# ws2812_Triangle.net
KiCad netlist of a schematic drawn in EAGLE
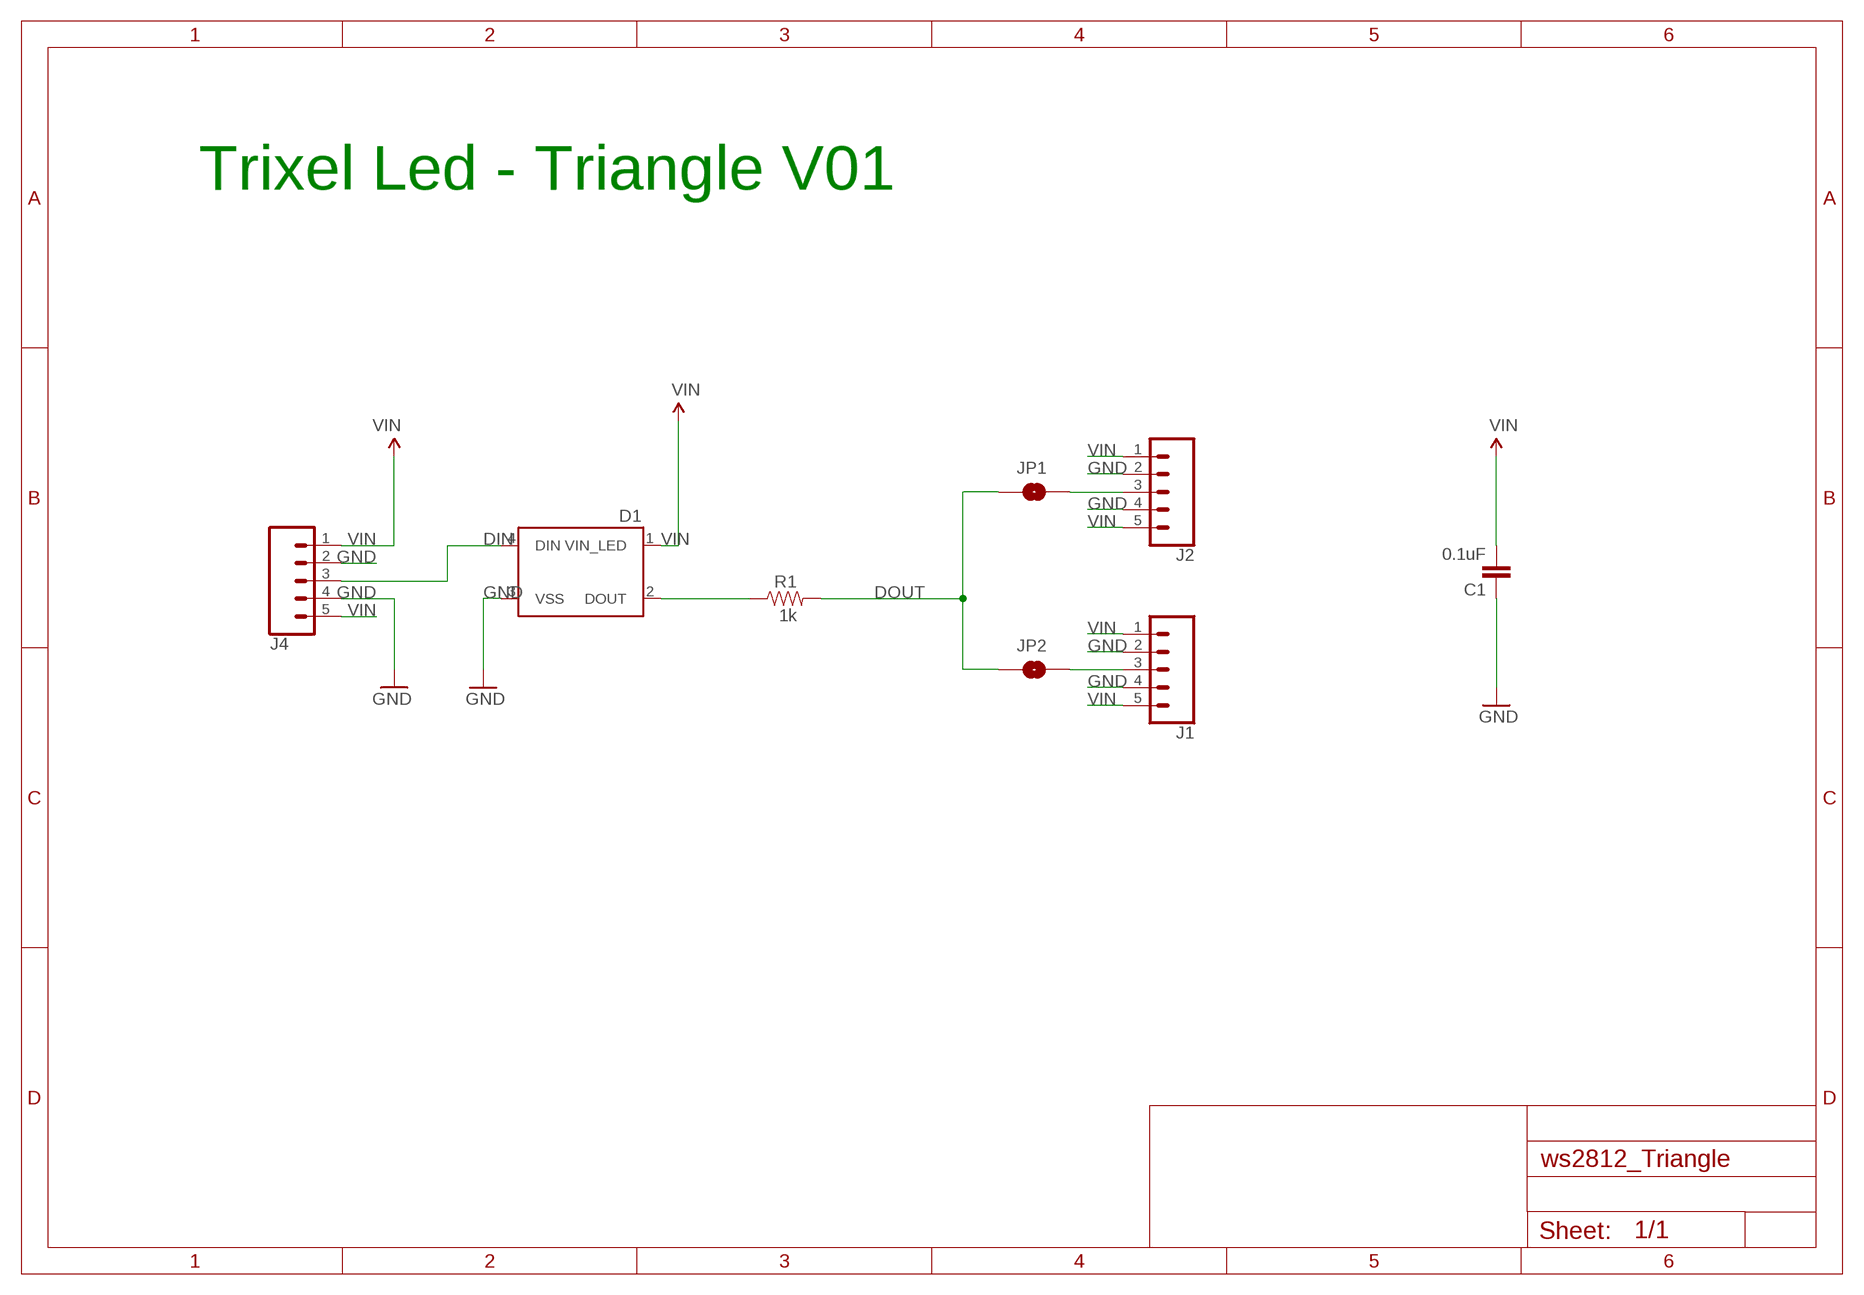
[diagram p0: schematic, sheet 1]

(export (version "E")
  (design (tool "Eeschema 10.0.6"))
  (components
    (comp (ref "C1")
      (value "0.1uF")
      (footprint "eagle-import:0805")
      (libsource (lib "eagle-import") (part "CAP0805"))
    )
    (comp (ref "D1")
      (value "WS2812B")
      (footprint "eagle-import:WS2812B")
      (libsource (lib "eagle-import") (part "WS2812B"))
    )
    (comp (ref "J1")
      (value "CONN_05PTH_LONGPADS")
      (footprint "eagle-import:1X05_LONGPADS")
      (libsource (lib "eagle-import") (part "CONN_05PTH_LONGPADS"))
    )
    (comp (ref "J2")
      (value "CONN_05PTH_LONGPADS")
      (footprint "eagle-import:1X05_LONGPADS")
      (libsource (lib "eagle-import") (part "CONN_05PTH_LONGPADS"))
    )
    (comp (ref "J4")
      (value "CONN_05PTH_LONGPADS")
      (footprint "eagle-import:1X05_LONGPADS")
      (libsource (lib "eagle-import") (part "CONN_05PTH_LONGPADS"))
    )
    (comp (ref "JP1")
      (value "JUMPER-PAD-2-NOYES_SILK")
      (footprint "eagle-import:PAD-JUMPER-2-NO_YES_SILK")
      (libsource (lib "eagle-import") (part "JUMPER-PAD-2-NOYES_SILK"))
    )
    (comp (ref "JP2")
      (value "JUMPER-PAD-2-NOYES_SILK")
      (footprint "eagle-import:PAD-JUMPER-2-NO_YES_SILK")
      (libsource (lib "eagle-import") (part "JUMPER-PAD-2-NOYES_SILK"))
    )
    (comp (ref "R1")
      (value "1k")
      (footprint "eagle-import:0805")
      (libsource (lib "eagle-import") (part "RESISTOR0805"))
    )
  )
  (nets
    (net (code "1") (name "/DIN") (class "Default")
      (node (ref "D1") (pin "4") (pinfunction "DIN_4") (pintype "input"))
      (node (ref "J4") (pin "3") (pinfunction "3_3") (pintype "passive"))
    )
    (net (code "2") (name "/DOUT") (class "Default")
      (node (ref "JP1") (pin "1") (pinfunction "1_1") (pintype "passive"))
      (node (ref "JP2") (pin "1") (pinfunction "1_1") (pintype "passive"))
      (node (ref "R1") (pin "2") (pinfunction "2_2") (pintype "passive"))
    )
    (net (code "3") (name "GND") (class "Default")
      (node (ref "C1") (pin "1") (pinfunction "1_1") (pintype "passive"))
      (node (ref "D1") (pin "3") (pinfunction "VSS_3") (pintype "power_in"))
      (node (ref "J1") (pin "2") (pinfunction "2_2") (pintype "passive"))
      (node (ref "J1") (pin "4") (pinfunction "4_4") (pintype "passive"))
      (node (ref "J2") (pin "2") (pinfunction "2_2") (pintype "passive"))
      (node (ref "J2") (pin "4") (pinfunction "4_4") (pintype "passive"))
      (node (ref "J4") (pin "2") (pinfunction "2_2") (pintype "passive"))
      (node (ref "J4") (pin "4") (pinfunction "4_4") (pintype "passive"))
    )
    (net (code "4") (name "Net-(D1-DOUT)") (class "Default")
      (node (ref "D1") (pin "2") (pinfunction "DOUT_2") (pintype "output"))
      (node (ref "R1") (pin "1") (pinfunction "1_1") (pintype "passive"))
    )
    (net (code "5") (name "Net-(J1-Pad3)") (class "Default")
      (node (ref "J1") (pin "3") (pinfunction "3_3") (pintype "passive"))
      (node (ref "JP2") (pin "2") (pinfunction "2_2") (pintype "passive"))
    )
    (net (code "6") (name "Net-(J2-Pad3)") (class "Default")
      (node (ref "J2") (pin "3") (pinfunction "3_3") (pintype "passive"))
      (node (ref "JP1") (pin "2") (pinfunction "2_2") (pintype "passive"))
    )
    (net (code "7") (name "VIN") (class "Default")
      (node (ref "C1") (pin "2") (pinfunction "2_2") (pintype "passive"))
      (node (ref "D1") (pin "1") (pinfunction "VIN_LED_1") (pintype "power_in"))
      (node (ref "J1") (pin "1") (pinfunction "1_1") (pintype "passive"))
      (node (ref "J1") (pin "5") (pinfunction "5_5") (pintype "passive"))
      (node (ref "J2") (pin "1") (pinfunction "1_1") (pintype "passive"))
      (node (ref "J2") (pin "5") (pinfunction "5_5") (pintype "passive"))
      (node (ref "J4") (pin "1") (pinfunction "1_1") (pintype "passive"))
      (node (ref "J4") (pin "5") (pinfunction "5_5") (pintype "passive"))
    )
  )
)
